# magnilamp_led.net
KiCad netlist of a schematic drawn in EAGLE
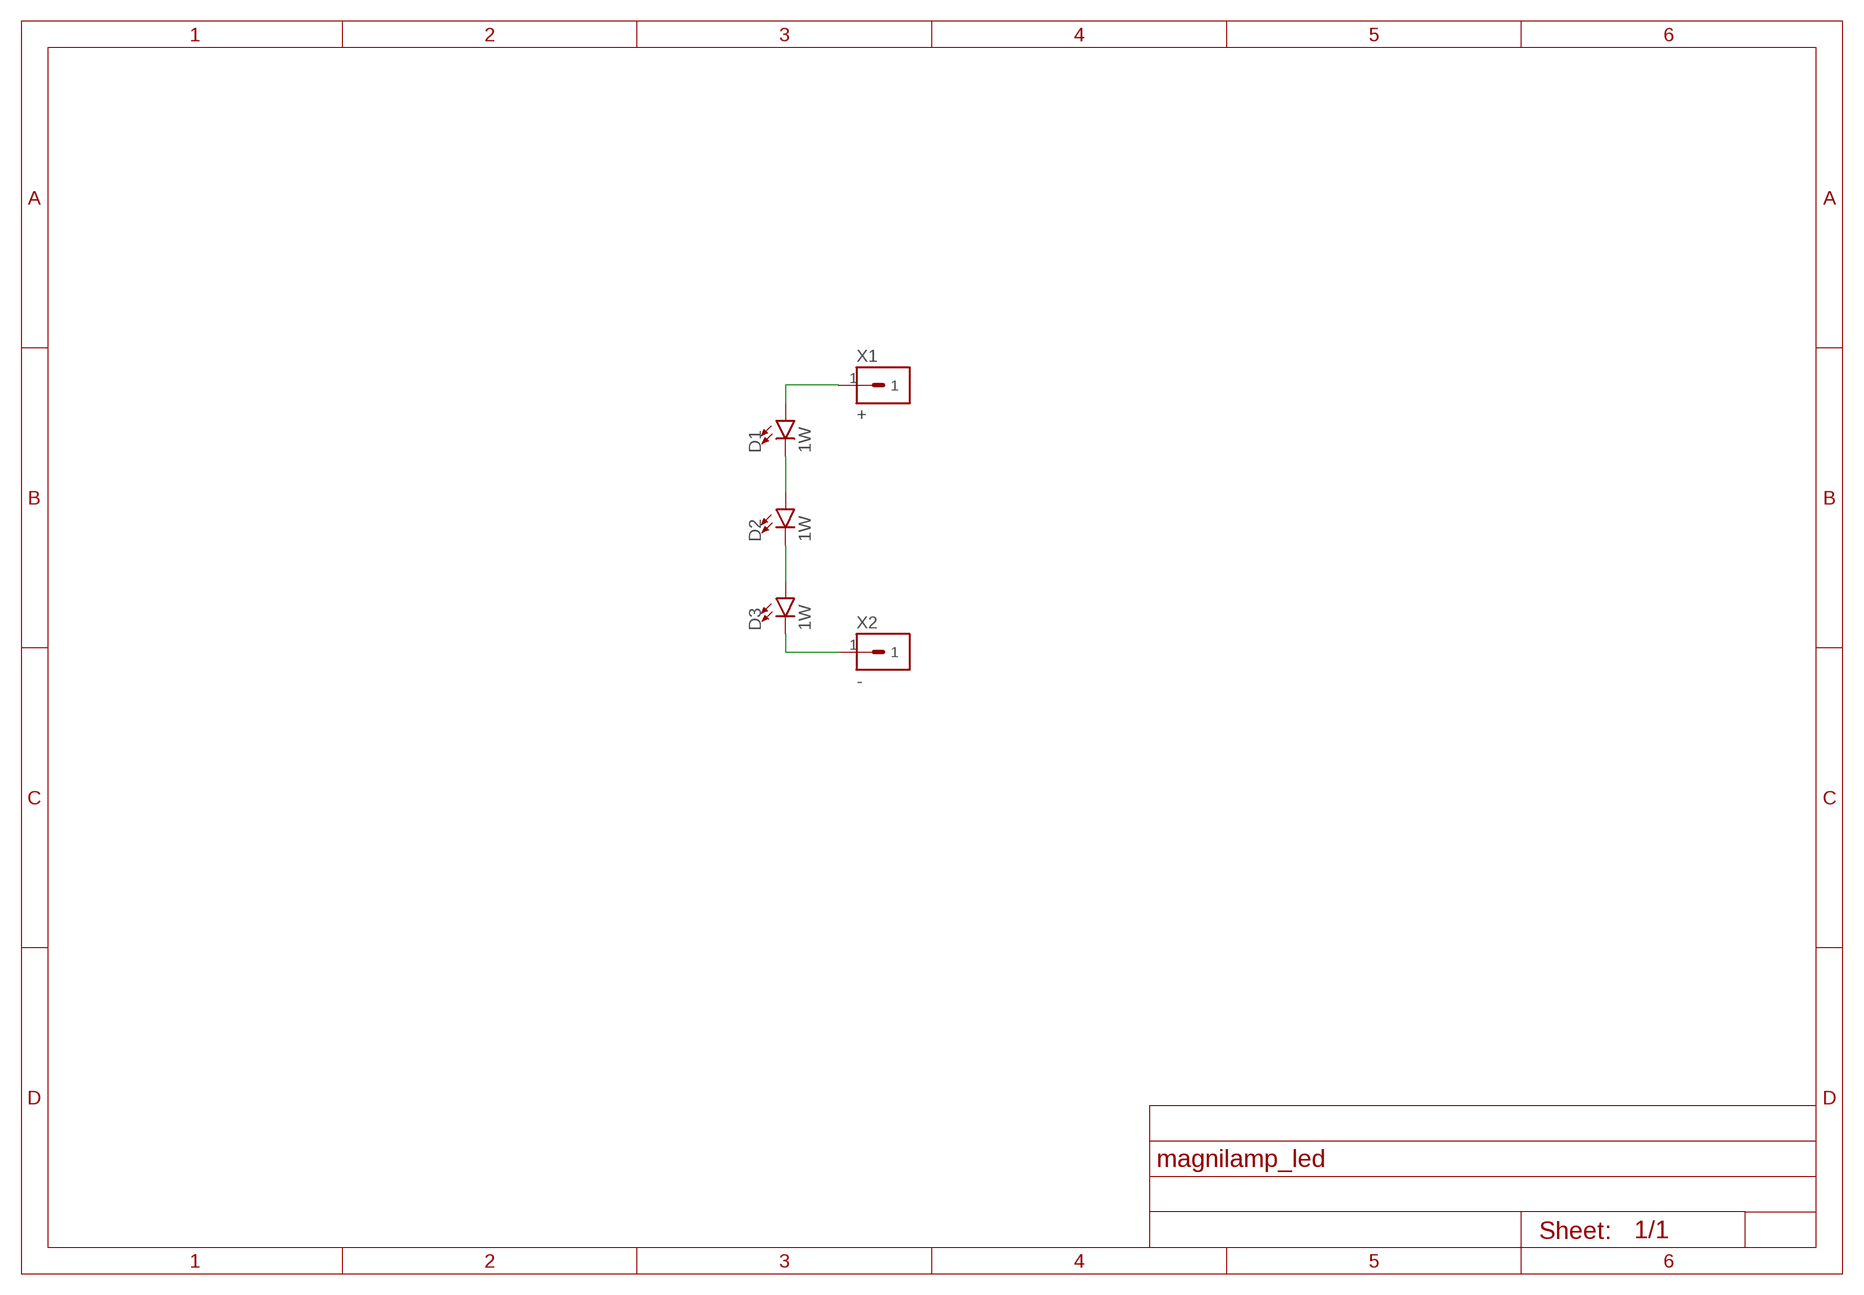
[diagram p0: schematic, sheet 1]

(export (version "E")
  (design (tool "Eeschema 10.0.6"))
  (components
    (comp (ref "D1")
      (value "1W")
      (footprint "eagle-import:LED_1W")
      (libsource (lib "eagle-import") (part "LED1W"))
    )
    (comp (ref "D2")
      (value "1W")
      (footprint "eagle-import:LED_1W")
      (libsource (lib "eagle-import") (part "LED1W"))
    )
    (comp (ref "D3")
      (value "1W")
      (footprint "eagle-import:LED_1W")
      (libsource (lib "eagle-import") (part "LED1W"))
    )
    (comp (ref "X1")
      (value "+")
      (footprint "eagle-import:SOLDERPAD-4X5")
      (libsource (lib "eagle-import") (part "SOLDERPAD4X5"))
    )
    (comp (ref "X2")
      (value "-")
      (footprint "eagle-import:SOLDERPAD-4X5")
      (libsource (lib "eagle-import") (part "SOLDERPAD4X5"))
    )
  )
  (nets
    (net (code "1") (name "Net-(D1-PadA)") (class "Default")
      (node (ref "D1") (pin "A") (pinfunction "A_A") (pintype "passive"))
      (node (ref "X1") (pin "1") (pinfunction "1_1") (pintype "passive"))
    )
    (net (code "2") (name "Net-(D1-PadC)") (class "Default")
      (node (ref "D1") (pin "C") (pinfunction "C_C") (pintype "passive"))
      (node (ref "D2") (pin "A") (pinfunction "A_A") (pintype "passive"))
    )
    (net (code "3") (name "Net-(D2-PadC)") (class "Default")
      (node (ref "D2") (pin "C") (pinfunction "C_C") (pintype "passive"))
      (node (ref "D3") (pin "A") (pinfunction "A_A") (pintype "passive"))
    )
    (net (code "4") (name "Net-(D3-PadC)") (class "Default")
      (node (ref "D3") (pin "C") (pinfunction "C_C") (pintype "passive"))
      (node (ref "X2") (pin "1") (pinfunction "1_1") (pintype "passive"))
    )
  )
)
